# ESP_BASE.net
KiCad netlist of a schematic drawn in Altium Designer
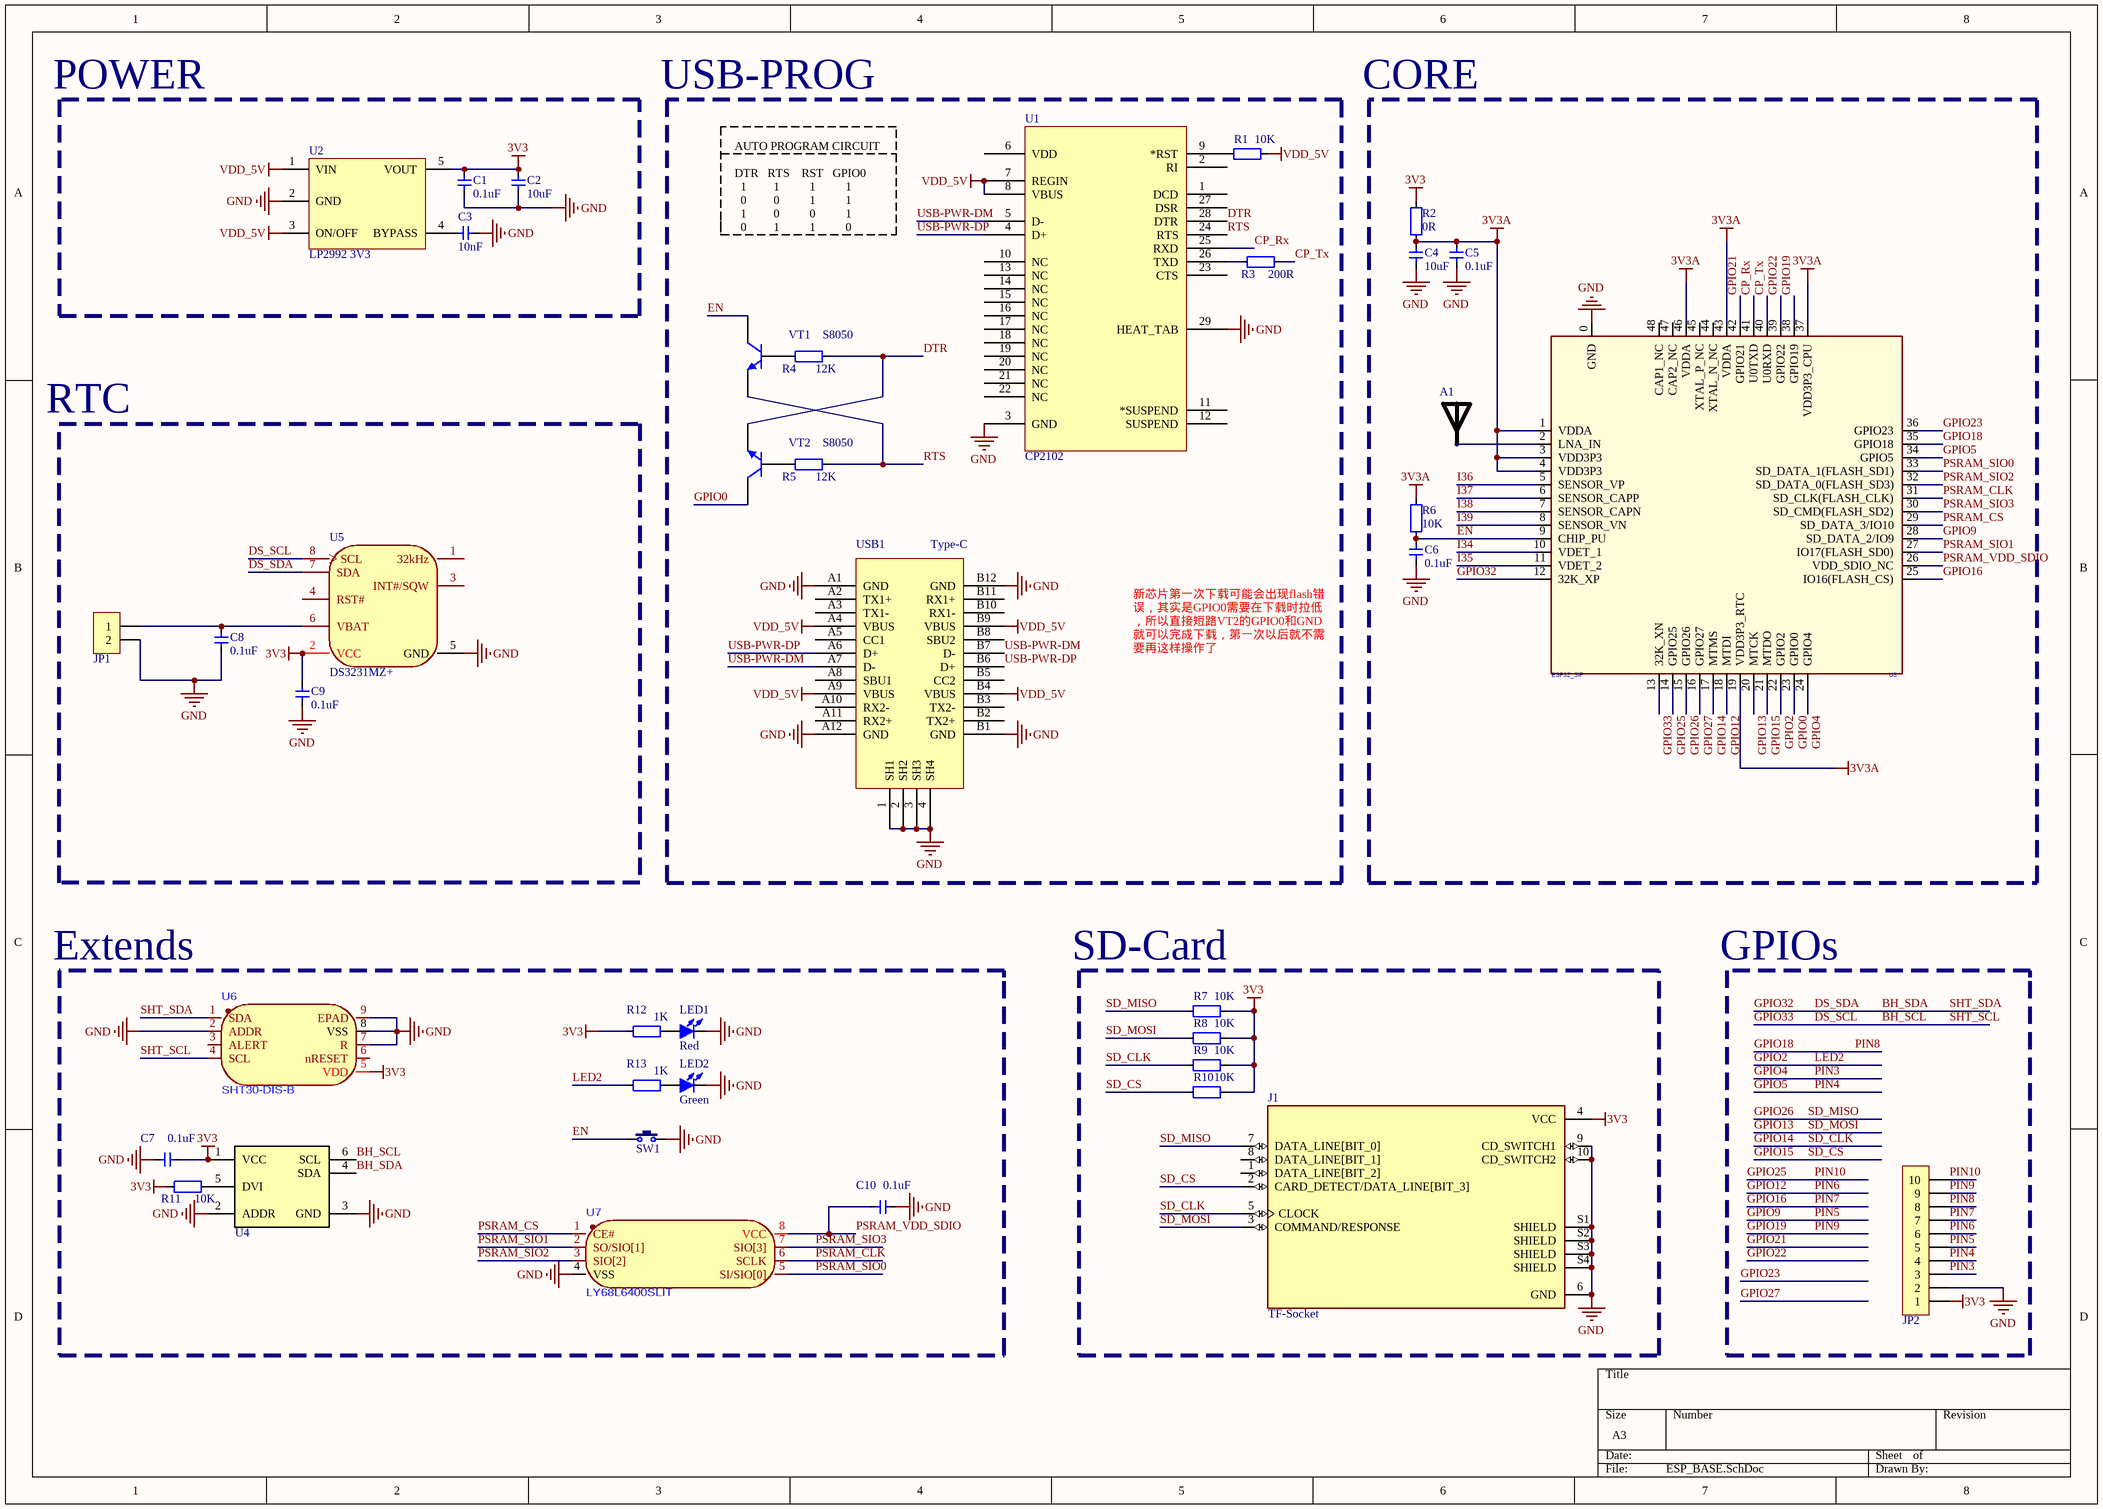
[diagram p0: ESP_BASE.SchDoc]

(export (version "E")
  (design (tool "Eeschema 10.0.6"))
  (components
    (comp (ref "A1")
      (value "RAINSUN")
      (footprint "ANT-Rainsun-AN5120")
      (libsource (lib "MyLib") (part "ANT-Rainsun-AP5120"))
    )
    (comp (ref "C1")
      (value "0.1uF")
      (footprint "CAP_0402")
      (description "Capacitor")
      (libsource (lib "MyLib") (part "电容-0402"))
    )
    (comp (ref "C2")
      (value "10uF")
      (footprint "CAP_0402")
      (description "Capacitor")
      (libsource (lib "MyLib") (part "电容-0402"))
    )
    (comp (ref "C3")
      (value "10nF")
      (footprint "CAP_0402")
      (description "Capacitor")
      (libsource (lib "MyLib") (part "电容-0402"))
    )
    (comp (ref "C4")
      (value "10uF")
      (footprint "CAP_0402")
      (description "Capacitor")
      (libsource (lib "MyLib") (part "电容-0402"))
    )
    (comp (ref "C5")
      (value "0.1uF")
      (footprint "CAP_0402")
      (description "Capacitor")
      (libsource (lib "MyLib") (part "电容-0402"))
    )
    (comp (ref "C6")
      (value "0.1uF")
      (footprint "CAP_0402")
      (description "Capacitor")
      (libsource (lib "MyLib") (part "电容-0402"))
    )
    (comp (ref "C7")
      (value "0.1uF")
      (footprint "CAP_0402")
      (description "Capacitor")
      (libsource (lib "MyLib") (part "电容-0402"))
    )
    (comp (ref "C8")
      (value "0.1uF")
      (footprint "CAP_0402")
      (description "Capacitor")
      (libsource (lib "MyLib") (part "电容-0402"))
    )
    (comp (ref "C9")
      (value "0.1uF")
      (footprint "CAP_0402")
      (description "Capacitor")
      (libsource (lib "MyLib") (part "电容-0402"))
    )
    (comp (ref "C10")
      (value "0.1uF")
      (footprint "CAP_0402")
      (description "Capacitor")
      (libsource (lib "MyLib") (part "电容-0402"))
    )
    (comp (ref "J1")
      (value "TF-Socket")
      (footprint "TF-Card-Amphenol with TF")
      (description "10 _8 + 2_ Position Card Connector Secure Digital - microSDâ„¢ Surface Mount, Right Angle Gold")
      (fields (field (name "MP") "1140084168") (field (name "MF") "Amphenol Commercial Products"))
      (libsource (lib "MyLib") (part "TF-Socket"))
    )
    (comp (ref "JP1")
      (value "MX 1.25-WS-2P")
      (footprint "MX 1.25-WS-2P")
      (description "2P接插件")
      (libsource (lib "MyLib") (part "MX 1.25-WS-2P"))
    )
    (comp (ref "JP2")
      (value "HDR-1X10")
      (footprint "HDR2.54-LI-10P")
      (description "10P接插件")
      (libsource (lib "MyLib") (part "Header 10"))
    )
    (comp (ref "LED1")
      (value "Red")
      (footprint "LED 0603R")
      (description "贴片LED")
      (libsource (lib "MyLib") (part "LED-SMD"))
    )
    (comp (ref "LED2")
      (value "Green")
      (footprint "LED 0603G")
      (description "贴片LED")
      (libsource (lib "MyLib") (part "LED-SMD"))
    )
    (comp (ref "R1")
      (value "10K")
      (footprint "RES_0402")
      (description "Resistor")
      (libsource (lib "MyLib") (part "电阻-0402"))
    )
    (comp (ref "R2")
      (value "0R")
      (footprint "RES_0402")
      (description "Resistor")
      (libsource (lib "") (part "电阻-0402_1"))
    )
    (comp (ref "R3")
      (value "200R")
      (footprint "RES_0402")
      (description "Resistor")
      (libsource (lib "MyLib") (part "电阻-0402"))
    )
    (comp (ref "R4")
      (value "12K")
      (footprint "RES_0402")
      (description "Resistor")
      (libsource (lib "MyLib") (part "电阻-0402"))
    )
    (comp (ref "R5")
      (value "12K")
      (footprint "RES_0402")
      (description "Resistor")
      (libsource (lib "MyLib") (part "电阻-0402"))
    )
    (comp (ref "R6")
      (value "10K")
      (footprint "RES_0402")
      (description "Resistor")
      (libsource (lib "") (part "电阻-0402_1"))
    )
    (comp (ref "R7")
      (value "10K")
      (footprint "RES_0402")
      (description "Resistor")
      (libsource (lib "MyLib") (part "电阻-0402"))
    )
    (comp (ref "R8")
      (value "10K")
      (footprint "RES_0402")
      (description "Resistor")
      (libsource (lib "MyLib") (part "电阻-0402"))
    )
    (comp (ref "R9")
      (value "10K")
      (footprint "RES_0402")
      (description "Resistor")
      (libsource (lib "MyLib") (part "电阻-0402"))
    )
    (comp (ref "R10")
      (value "10K")
      (footprint "RES_0402")
      (description "Resistor")
      (libsource (lib "MyLib") (part "电阻-0402"))
    )
    (comp (ref "R11")
      (value "10K")
      (footprint "RES_0402")
      (description "Resistor")
      (libsource (lib "MyLib") (part "电阻-0402"))
    )
    (comp (ref "R12")
      (value "1K")
      (footprint "RES_0402")
      (description "Resistor")
      (libsource (lib "MyLib") (part "电阻-0402"))
    )
    (comp (ref "R13")
      (value "1K")
      (footprint "RES_0402")
      (description "Resistor")
      (libsource (lib "MyLib") (part "电阻-0402"))
    )
    (comp (ref "SW1")
      (value "3x6x5")
      (footprint "TSW SMD-3*6*2.5")
      (description "3x6轻触开关")
      (libsource (lib "MyLib") (part "TSW 3x6"))
    )
    (comp (ref "U1")
      (value "CP2102")
      (footprint "QFN-28")
      (description "USB转TTL")
      (libsource (lib "MyLib") (part "CP2102"))
    )
    (comp (ref "U2")
      (value "LP2992 3V3")
      (footprint "SOT23-5")
      (description "LDO")
      (libsource (lib "MyLib") (part "LP2992"))
    )
    (comp (ref "U3")
      (value "ESP32_SIP")
      (footprint "QFN-48_7X7")
      (libsource (lib "MyLib") (part "ESP32-PICO"))
    )
    (comp (ref "U4")
      (value "BH1750FVI-TR")
      (footprint "BH1750FVI")
      (libsource (lib "MyLib") (part "BH1750FVI-TR"))
    )
    (comp (ref "U5") (value "DS3231MZ+") (footprint "SO8_L") (libsource (lib "MyLib") (part "DS3231MZ+")))
    (comp (ref "U6")
      (value "SHT30-DIS-B")
      (footprint "DFN-8_L2.5-W2.5-P0.50-BL-EP")
      (libsource (lib "MyLib") (part "SHT30-DIS-B"))
    )
    (comp (ref "U7")
      (value "LY68L6400SLIT")
      (footprint "SOP-8_150MIL")
      (description "PSRAM")
      (libsource (lib "MyLib") (part "LY68L6400SLIT"))
    )
    (comp (ref "USB1")
      (value "Type-C")
      (footprint "Type-C-TOP")
      (libsource (lib "MyLib") (part "USB-Type-C-TOP"))
    )
    (comp (ref "VT1")
      (value "S8050")
      (footprint "SMT_TRIODE_NPN")
      (description "Surface mount NPN transistor, package SOT-23")
      (libsource (lib "MyLib") (part "SMT_TRIODE_NPN"))
    )
    (comp (ref "VT2")
      (value "S8050")
      (footprint "SMT_TRIODE_NPN")
      (description "Surface mount NPN transistor, package SOT-23")
      (libsource (lib "MyLib") (part "SMT_TRIODE_NPN"))
    )
  )
  (nets
    (net (code "1") (name "/BH_SCL") (class "Default")
      (node (ref "U3") (pin "13") (pinfunction "32K_XN_13") (pintype "passive"))
      (node (ref "U4") (pin "6") (pinfunction "SCL_6") (pintype "passive"))
      (node (ref "U5") (pin "8") (pinfunction "SCL_8") (pintype "passive"))
      (node (ref "U6") (pin "4") (pinfunction "SCL_4") (pintype "passive"))
    )
    (net (code "2") (name "/BH_SDA") (class "Default")
      (node (ref "U3") (pin "12") (pinfunction "32K_XP_12") (pintype "passive"))
      (node (ref "U4") (pin "4") (pinfunction "SDA_4") (pintype "passive"))
      (node (ref "U5") (pin "7") (pinfunction "SDA_7") (pintype "passive"))
      (node (ref "U6") (pin "1") (pinfunction "SDA_1") (pintype "passive"))
    )
    (net (code "3") (name "/CP_Rx") (class "Default")
      (node (ref "U1") (pin "25") (pinfunction "RXD_25") (pintype "passive"))
      (node (ref "U3") (pin "41") (pinfunction "U0TXD_41") (pintype "power_in"))
    )
    (net (code "4") (name "/CP_Tx") (class "Default")
      (node (ref "R3") (pin "1") (pinfunction "1_1") (pintype "passive"))
      (node (ref "U3") (pin "40") (pinfunction "U0RXD_40") (pintype "power_in"))
    )
    (net (code "5") (name "/DTR") (class "Default")
      (node (ref "R4") (pin "1") (pinfunction "1_1") (pintype "passive"))
      (node (ref "U1") (pin "28") (pinfunction "DTR_28") (pintype "passive"))
      (node (ref "VT2") (pin "2") (pinfunction "E_2") (pintype "passive"))
    )
    (net (code "6") (name "/EN") (class "Default")
      (node (ref "C6") (pin "1") (pinfunction "1_1") (pintype "passive"))
      (node (ref "R6") (pin "2") (pinfunction "2_2") (pintype "passive"))
      (node (ref "SW1") (pin "1") (pinfunction "1_1") (pintype "passive"))
      (node (ref "U3") (pin "9") (pinfunction "CHIP_PU_9") (pintype "passive"))
      (node (ref "VT1") (pin "3") (pinfunction "C_3") (pintype "passive"))
    )
    (net (code "7") (name "/GPIO0") (class "Default")
      (node (ref "U3") (pin "23") (pinfunction "GPIO0_23") (pintype "passive"))
      (node (ref "VT2") (pin "3") (pinfunction "C_3") (pintype "passive"))
    )
    (net (code "8") (name "/GPIO2") (class "Default")
      (node (ref "R13") (pin "2") (pinfunction "2_2") (pintype "passive"))
      (node (ref "U3") (pin "22") (pinfunction "GPIO2_22") (pintype "passive"))
    )
    (net (code "9") (name "/GPIO4") (class "Default")
      (node (ref "JP2") (pin "3") (pinfunction "3_3") (pintype "passive"))
      (node (ref "U3") (pin "24") (pinfunction "GPIO4_24") (pintype "passive"))
    )
    (net (code "10") (name "/GPIO5") (class "Default")
      (node (ref "JP2") (pin "4") (pinfunction "4_4") (pintype "passive"))
      (node (ref "U3") (pin "34") (pinfunction "GPIO5_34") (pintype "passive"))
    )
    (net (code "11") (name "/GPIO9") (class "Default")
      (node (ref "JP2") (pin "5") (pinfunction "5_5") (pintype "passive"))
      (node (ref "U3") (pin "28") (pinfunction "SD_DATA_2/IO9_28") (pintype "passive"))
    )
    (net (code "12") (name "/GPIO12") (class "Default")
      (node (ref "JP2") (pin "6") (pinfunction "6_6") (pintype "passive"))
      (node (ref "U3") (pin "18") (pinfunction "MTDI_18") (pintype "passive"))
    )
    (net (code "13") (name "/GPIO13") (class "Default")
      (node (ref "J1") (pin "3") (pinfunction "COMMAND/RESPONSE_3") (pintype "bidirectional"))
      (node (ref "R8") (pin "2") (pinfunction "2_2") (pintype "passive"))
      (node (ref "U3") (pin "20") (pinfunction "MTCK_20") (pintype "passive"))
    )
    (net (code "14") (name "/GPIO14") (class "Default")
      (node (ref "J1") (pin "5") (pinfunction "CLOCK_5") (pintype "bidirectional"))
      (node (ref "R9") (pin "2") (pinfunction "2_2") (pintype "passive"))
      (node (ref "U3") (pin "17") (pinfunction "MTMS_17") (pintype "passive"))
    )
    (net (code "15") (name "/GPIO15") (class "Default")
      (node (ref "J1") (pin "2") (pinfunction "CARD_DETECT/DATA_LINE[BIT_3]_2") (pintype "bidirectional"))
      (node (ref "R10") (pin "2") (pinfunction "2_2") (pintype "passive"))
      (node (ref "U3") (pin "21") (pinfunction "MTDO_21") (pintype "passive"))
    )
    (net (code "16") (name "/GPIO16") (class "Default")
      (node (ref "JP2") (pin "7") (pinfunction "7_7") (pintype "passive"))
      (node (ref "U3") (pin "25") (pinfunction "IO16(FLASH_CS)_25") (pintype "passive"))
    )
    (net (code "17") (name "/GPIO18") (class "Default")
      (node (ref "JP2") (pin "8") (pinfunction "8_8") (pintype "passive"))
      (node (ref "U3") (pin "35") (pinfunction "GPIO18_35") (pintype "passive"))
    )
    (net (code "18") (name "/GPIO19") (class "Default")
      (node (ref "JP2") (pin "9") (pinfunction "9_9") (pintype "passive"))
      (node (ref "U3") (pin "38") (pinfunction "GPIO19_38") (pintype "passive"))
    )
    (net (code "19") (name "/GPIO21") (class "Default")
      (node (ref "U3") (pin "42") (pinfunction "GPIO21_42") (pintype "passive"))
    )
    (net (code "20") (name "/GPIO22") (class "Default")
      (node (ref "U3") (pin "39") (pinfunction "GPIO22_39") (pintype "passive"))
    )
    (net (code "21") (name "/GPIO23") (class "Default")
      (node (ref "U3") (pin "36") (pinfunction "GPIO23_36") (pintype "passive"))
    )
    (net (code "22") (name "/GPIO25") (class "Default")
      (node (ref "JP2") (pin "10") (pinfunction "10_10") (pintype "passive"))
      (node (ref "U3") (pin "14") (pinfunction "GPIO25_14") (pintype "passive"))
    )
    (net (code "23") (name "/GPIO26") (class "Default")
      (node (ref "J1") (pin "7") (pinfunction "DATA_LINE[BIT_0]_7") (pintype "bidirectional"))
      (node (ref "R7") (pin "2") (pinfunction "2_2") (pintype "passive"))
      (node (ref "U3") (pin "15") (pinfunction "GPIO26_15") (pintype "passive"))
    )
    (net (code "24") (name "/GPIO27") (class "Default")
      (node (ref "U3") (pin "16") (pinfunction "GPIO27_16") (pintype "passive"))
    )
    (net (code "25") (name "/I34") (class "Default")
      (node (ref "U3") (pin "10") (pinfunction "VDET_1_10") (pintype "passive"))
    )
    (net (code "26") (name "/I35") (class "Default")
      (node (ref "U3") (pin "11") (pinfunction "VDET_2_11") (pintype "passive"))
    )
    (net (code "27") (name "/I36") (class "Default")
      (node (ref "U3") (pin "5") (pinfunction "SENSOR_VP_5") (pintype "passive"))
    )
    (net (code "28") (name "/I37") (class "Default")
      (node (ref "U3") (pin "6") (pinfunction "SENSOR_CAPP_6") (pintype "passive"))
    )
    (net (code "29") (name "/I38") (class "Default")
      (node (ref "U3") (pin "7") (pinfunction "SENSOR_CAPN_7") (pintype "passive"))
    )
    (net (code "30") (name "/I39") (class "Default")
      (node (ref "U3") (pin "8") (pinfunction "SENSOR_VN_8") (pintype "passive"))
    )
    (net (code "31") (name "/PSRAM_CLK") (class "Default")
      (node (ref "U3") (pin "31") (pinfunction "SD_CLK(FLASH_CLK)_31") (pintype "passive"))
      (node (ref "U7") (pin "6") (pinfunction "SCLK_6") (pintype "passive"))
    )
    (net (code "32") (name "/PSRAM_CS") (class "Default")
      (node (ref "U3") (pin "29") (pinfunction "SD_DATA_3/IO10_29") (pintype "passive"))
      (node (ref "U7") (pin "1") (pinfunction "CE#_1") (pintype "passive"))
    )
    (net (code "33") (name "/PSRAM_SIO0") (class "Default")
      (node (ref "U3") (pin "33") (pinfunction "SD_DATA_1(FLASH_SD1)_33") (pintype "passive"))
      (node (ref "U7") (pin "5") (pinfunction "SI/SIO[0]_5") (pintype "passive"))
    )
    (net (code "34") (name "/PSRAM_SIO1") (class "Default")
      (node (ref "U3") (pin "27") (pinfunction "IO17(FLASH_SD0)_27") (pintype "passive"))
      (node (ref "U7") (pin "2") (pinfunction "SO/SIO[1]_2") (pintype "passive"))
    )
    (net (code "35") (name "/PSRAM_SIO2") (class "Default")
      (node (ref "U3") (pin "32") (pinfunction "SD_DATA_0(FLASH_SD3)_32") (pintype "passive"))
      (node (ref "U7") (pin "3") (pinfunction "SIO[2]_3") (pintype "passive"))
    )
    (net (code "36") (name "/PSRAM_SIO3") (class "Default")
      (node (ref "U3") (pin "30") (pinfunction "SD_CMD(FLASH_SD2)_30") (pintype "passive"))
      (node (ref "U7") (pin "7") (pinfunction "SIO[3]_7") (pintype "passive"))
    )
    (net (code "37") (name "/PSRAM_VDD_SDIO") (class "Default")
      (node (ref "C10") (pin "2") (pinfunction "2_2") (pintype "passive"))
      (node (ref "U3") (pin "26") (pinfunction "VDD_SDIO_NC_26") (pintype "passive"))
      (node (ref "U7") (pin "8") (pinfunction "VCC_8") (pintype "passive"))
    )
    (net (code "38") (name "/RTS") (class "Default")
      (node (ref "R5") (pin "1") (pinfunction "1_1") (pintype "passive"))
      (node (ref "U1") (pin "24") (pinfunction "RTS_24") (pintype "passive"))
      (node (ref "VT1") (pin "2") (pinfunction "E_2") (pintype "passive"))
    )
    (net (code "39") (name "/USB-PWR-DM") (class "Default")
      (node (ref "U1") (pin "5") (pinfunction "D-_5") (pintype "passive"))
      (node (ref "USB1") (pin "A7") (pinfunction "D-_A7") (pintype "passive"))
      (node (ref "USB1") (pin "B7") (pinfunction "D-_B7") (pintype "passive"))
    )
    (net (code "40") (name "/USB-PWR-DP") (class "Default")
      (node (ref "U1") (pin "4") (pinfunction "D+_4") (pintype "passive"))
      (node (ref "USB1") (pin "A6") (pinfunction "D+_A6") (pintype "passive"))
      (node (ref "USB1") (pin "B6") (pinfunction "D+_B6") (pintype "passive"))
    )
    (net (code "41") (name "3V3") (class "Default")
      (node (ref "C1") (pin "2") (pinfunction "2_2") (pintype "passive"))
      (node (ref "C2") (pin "2") (pinfunction "2_2") (pintype "passive"))
      (node (ref "C7") (pin "1") (pinfunction "1_1") (pintype "passive"))
      (node (ref "C9") (pin "1") (pinfunction "1_1") (pintype "passive"))
      (node (ref "J1") (pin "4") (pinfunction "VCC_4") (pintype "power_in"))
      (node (ref "JP2") (pin "1") (pinfunction "1_1") (pintype "passive"))
      (node (ref "R10") (pin "1") (pinfunction "1_1") (pintype "passive"))
      (node (ref "R11") (pin "2") (pinfunction "2_2") (pintype "passive"))
      (node (ref "R12") (pin "2") (pinfunction "2_2") (pintype "passive"))
      (node (ref "R2") (pin "1") (pinfunction "1_1") (pintype "passive"))
      (node (ref "R7") (pin "1") (pinfunction "1_1") (pintype "passive"))
      (node (ref "R8") (pin "1") (pinfunction "1_1") (pintype "passive"))
      (node (ref "R9") (pin "1") (pinfunction "1_1") (pintype "passive"))
      (node (ref "U2") (pin "5") (pinfunction "VOUT_5") (pintype "passive"))
      (node (ref "U4") (pin "1") (pinfunction "VCC_1") (pintype "passive"))
      (node (ref "U5") (pin "2") (pinfunction "VCC_2") (pintype "passive"))
      (node (ref "U6") (pin "5") (pinfunction "VDD_5") (pintype "passive"))
    )
    (net (code "42") (name "3V3A") (class "Default")
      (node (ref "C4") (pin "2") (pinfunction "2_2") (pintype "passive"))
      (node (ref "C5") (pin "2") (pinfunction "2_2") (pintype "passive"))
      (node (ref "R2") (pin "2") (pinfunction "2_2") (pintype "passive"))
      (node (ref "R6") (pin "1") (pinfunction "1_1") (pintype "passive"))
      (node (ref "U3") (pin "1") (pinfunction "VDDA_1") (pintype "power_in"))
      (node (ref "U3") (pin "19") (pinfunction "VDD3P3_RTC_19") (pintype "power_in"))
      (node (ref "U3") (pin "3") (pinfunction "VDD3P3_3") (pintype "power_in"))
      (node (ref "U3") (pin "37") (pinfunction "VDD3P3_CPU_37") (pintype "power_in"))
      (node (ref "U3") (pin "4") (pinfunction "VDD3P3_4") (pintype "power_in"))
      (node (ref "U3") (pin "43") (pinfunction "VDDA_43") (pintype "power_in"))
      (node (ref "U3") (pin "46") (pinfunction "VDDA_46") (pintype "power_in"))
    )
    (net (code "43") (name "GND") (class "Default")
      (node (ref "C1") (pin "1") (pinfunction "1_1") (pintype "passive"))
      (node (ref "C10") (pin "1") (pinfunction "1_1") (pintype "passive"))
      (node (ref "C2") (pin "1") (pinfunction "1_1") (pintype "passive"))
      (node (ref "C3") (pin "1") (pinfunction "1_1") (pintype "passive"))
      (node (ref "C4") (pin "1") (pinfunction "1_1") (pintype "passive"))
      (node (ref "C5") (pin "1") (pinfunction "1_1") (pintype "passive"))
      (node (ref "C6") (pin "2") (pinfunction "2_2") (pintype "passive"))
      (node (ref "C7") (pin "2") (pinfunction "2_2") (pintype "passive"))
      (node (ref "C8") (pin "2") (pinfunction "2_2") (pintype "passive"))
      (node (ref "C9") (pin "2") (pinfunction "2_2") (pintype "passive"))
      (node (ref "J1") (pin "10") (pinfunction "CD_SWITCH2_10") (pintype "bidirectional"))
      (node (ref "J1") (pin "6") (pinfunction "GND_6") (pintype "power_in"))
      (node (ref "J1") (pin "9") (pinfunction "CD_SWITCH1_9") (pintype "bidirectional"))
      (node (ref "J1") (pin "S1") (pinfunction "SHIELD_S1") (pintype "passive"))
      (node (ref "J1") (pin "S2") (pinfunction "SHIELD_S2") (pintype "passive"))
      (node (ref "J1") (pin "S3") (pinfunction "SHIELD_S3") (pintype "passive"))
      (node (ref "J1") (pin "S4") (pinfunction "SHIELD_S4") (pintype "passive"))
      (node (ref "JP1") (pin "2") (pinfunction "2_2") (pintype "passive"))
      (node (ref "JP2") (pin "2") (pinfunction "2_2") (pintype "passive"))
      (node (ref "LED1") (pin "2") (pinfunction "K_2") (pintype "passive"))
      (node (ref "LED2") (pin "2") (pinfunction "K_2") (pintype "passive"))
      (node (ref "SW1") (pin "2") (pinfunction "2_2") (pintype "passive"))
      (node (ref "U1") (pin "29") (pinfunction "HEAT_TAB_29") (pintype "passive"))
      (node (ref "U1") (pin "3") (pinfunction "GND_3") (pintype "passive"))
      (node (ref "U2") (pin "2") (pinfunction "GND_2") (pintype "passive"))
      (node (ref "U3") (pin "0") (pinfunction "GND_0") (pintype "power_in"))
      (node (ref "U4") (pin "2") (pinfunction "ADDR_2") (pintype "passive"))
      (node (ref "U4") (pin "3") (pinfunction "GND_3") (pintype "passive"))
      (node (ref "U5") (pin "5") (pinfunction "GND_5") (pintype "passive"))
      (node (ref "U6") (pin "2") (pinfunction "ADDR_2") (pintype "passive"))
      (node (ref "U6") (pin "7") (pinfunction "R_7") (pintype "passive"))
      (node (ref "U6") (pin "8") (pinfunction "VSS_8") (pintype "passive"))
      (node (ref "U6") (pin "9") (pinfunction "EPAD_9") (pintype "passive"))
      (node (ref "U7") (pin "4") (pinfunction "VSS_4") (pintype "passive"))
      (node (ref "USB1") (pin "1") (pinfunction "SH1_1") (pintype "passive"))
      (node (ref "USB1") (pin "2") (pinfunction "SH2_2") (pintype "passive"))
      (node (ref "USB1") (pin "3") (pinfunction "SH3_3") (pintype "passive"))
      (node (ref "USB1") (pin "4") (pinfunction "SH4_4") (pintype "passive"))
      (node (ref "USB1") (pin "A1") (pinfunction "GND_A1") (pintype "passive"))
      (node (ref "USB1") (pin "A12") (pinfunction "GND_A12") (pintype "passive"))
      (node (ref "USB1") (pin "B1") (pinfunction "GND_B1") (pintype "passive"))
      (node (ref "USB1") (pin "B12") (pinfunction "GND_B12") (pintype "passive"))
    )
    (net (code "44") (name "Net-(LED1-A)") (class "Default")
      (node (ref "LED1") (pin "1") (pinfunction "A_1") (pintype "passive"))
      (node (ref "R12") (pin "1") (pinfunction "1_1") (pintype "passive"))
    )
    (net (code "45") (name "Net-(LED2-A)") (class "Default")
      (node (ref "LED2") (pin "1") (pinfunction "A_1") (pintype "passive"))
      (node (ref "R13") (pin "1") (pinfunction "1_1") (pintype "passive"))
    )
    (net (code "46") (name "Net-(U1-*RST)") (class "Default")
      (node (ref "R1") (pin "2") (pinfunction "2_2") (pintype "passive"))
      (node (ref "U1") (pin "9") (pinfunction "*RST_9") (pintype "passive"))
    )
    (net (code "47") (name "Net-(U1-TXD)") (class "Default")
      (node (ref "R3") (pin "2") (pinfunction "2_2") (pintype "passive"))
      (node (ref "U1") (pin "26") (pinfunction "TXD_26") (pintype "passive"))
    )
    (net (code "48") (name "Net-(U2-BYPASS)") (class "Default")
      (node (ref "C3") (pin "2") (pinfunction "2_2") (pintype "passive"))
      (node (ref "U2") (pin "4") (pinfunction "BYPASS_4") (pintype "passive"))
    )
    (net (code "49") (name "Net-(U3-LNA_IN)") (class "Default")
      (node (ref "A1") (pin "1") (pinfunction "1_1") (pintype "passive"))
      (node (ref "U3") (pin "2") (pinfunction "LNA_IN_2") (pintype "passive"))
    )
    (net (code "50") (name "Net-(U4-DVI)") (class "Default")
      (node (ref "R11") (pin "1") (pinfunction "1_1") (pintype "passive"))
      (node (ref "U4") (pin "5") (pinfunction "DVI_5") (pintype "passive"))
    )
    (net (code "51") (name "Net-(U5-VBAT)") (class "Default")
      (node (ref "C8") (pin "1") (pinfunction "1_1") (pintype "passive"))
      (node (ref "JP1") (pin "1") (pinfunction "1_1") (pintype "passive"))
      (node (ref "U5") (pin "6") (pinfunction "VBAT_6") (pintype "passive"))
    )
    (net (code "52") (name "Net-(VT1-B)") (class "Default")
      (node (ref "R4") (pin "2") (pinfunction "2_2") (pintype "passive"))
      (node (ref "VT1") (pin "1") (pinfunction "B_1") (pintype "passive"))
    )
    (net (code "53") (name "Net-(VT2-B)") (class "Default")
      (node (ref "R5") (pin "2") (pinfunction "2_2") (pintype "passive"))
      (node (ref "VT2") (pin "1") (pinfunction "B_1") (pintype "passive"))
    )
    (net (code "54") (name "VDD_5V") (class "Default")
      (node (ref "R1") (pin "1") (pinfunction "1_1") (pintype "passive"))
      (node (ref "U1") (pin "7") (pinfunction "REGIN_7") (pintype "passive"))
      (node (ref "U1") (pin "8") (pinfunction "VBUS_8") (pintype "passive"))
      (node (ref "U2") (pin "1") (pinfunction "VIN_1") (pintype "passive"))
      (node (ref "U2") (pin "3") (pinfunction "ON/OFF_3") (pintype "passive"))
      (node (ref "USB1") (pin "A4") (pinfunction "VBUS_A4") (pintype "passive"))
      (node (ref "USB1") (pin "A9") (pinfunction "VBUS_A9") (pintype "passive"))
      (node (ref "USB1") (pin "B4") (pinfunction "VBUS_B4") (pintype "passive"))
      (node (ref "USB1") (pin "B9") (pinfunction "VBUS_B9") (pintype "passive"))
    )
    (net (code "55") (name "unconnected-(J1-DATA_LINE[BIT_1]-Pad8)") (class "Default")
      (node (ref "J1") (pin "8") (pinfunction "DATA_LINE[BIT_1]_8") (pintype "bidirectional"))
    )
    (net (code "56") (name "unconnected-(J1-DATA_LINE[BIT_2]-Pad1)") (class "Default")
      (node (ref "J1") (pin "1") (pinfunction "DATA_LINE[BIT_2]_1") (pintype "bidirectional"))
    )
    (net (code "57") (name "unconnected-(U1-*SUSPEND-Pad11)") (class "Default")
      (node (ref "U1") (pin "11") (pinfunction "*SUSPEND_11") (pintype "passive"))
    )
    (net (code "58") (name "unconnected-(U1-CTS-Pad23)") (class "Default")
      (node (ref "U1") (pin "23") (pinfunction "CTS_23") (pintype "passive"))
    )
    (net (code "59") (name "unconnected-(U1-DCD-Pad1)") (class "Default")
      (node (ref "U1") (pin "1") (pinfunction "DCD_1") (pintype "passive"))
    )
    (net (code "60") (name "unconnected-(U1-DSR-Pad27)") (class "Default")
      (node (ref "U1") (pin "27") (pinfunction "DSR_27") (pintype "passive"))
    )
    (net (code "61") (name "unconnected-(U1-NC-Pad10)") (class "Default")
      (node (ref "U1") (pin "10") (pinfunction "NC_10") (pintype "passive"))
    )
    (net (code "62") (name "unconnected-(U1-NC-Pad13)") (class "Default")
      (node (ref "U1") (pin "13") (pinfunction "NC_13") (pintype "passive"))
    )
    (net (code "63") (name "unconnected-(U1-NC-Pad14)") (class "Default")
      (node (ref "U1") (pin "14") (pinfunction "NC_14") (pintype "passive"))
    )
    (net (code "64") (name "unconnected-(U1-NC-Pad15)") (class "Default")
      (node (ref "U1") (pin "15") (pinfunction "NC_15") (pintype "passive"))
    )
    (net (code "65") (name "unconnected-(U1-NC-Pad16)") (class "Default")
      (node (ref "U1") (pin "16") (pinfunction "NC_16") (pintype "passive"))
    )
    (net (code "66") (name "unconnected-(U1-NC-Pad17)") (class "Default")
      (node (ref "U1") (pin "17") (pinfunction "NC_17") (pintype "passive"))
    )
    (net (code "67") (name "unconnected-(U1-NC-Pad18)") (class "Default")
      (node (ref "U1") (pin "18") (pinfunction "NC_18") (pintype "passive"))
    )
    (net (code "68") (name "unconnected-(U1-NC-Pad19)") (class "Default")
      (node (ref "U1") (pin "19") (pinfunction "NC_19") (pintype "passive"))
    )
    (net (code "69") (name "unconnected-(U1-NC-Pad20)") (class "Default")
      (node (ref "U1") (pin "20") (pinfunction "NC_20") (pintype "passive"))
    )
    (net (code "70") (name "unconnected-(U1-NC-Pad21)") (class "Default")
      (node (ref "U1") (pin "21") (pinfunction "NC_21") (pintype "passive"))
    )
    (net (code "71") (name "unconnected-(U1-NC-Pad22)") (class "Default")
      (node (ref "U1") (pin "22") (pinfunction "NC_22") (pintype "passive"))
    )
    (net (code "72") (name "unconnected-(U1-RI-Pad2)") (class "Default")
      (node (ref "U1") (pin "2") (pinfunction "RI_2") (pintype "passive"))
    )
    (net (code "73") (name "unconnected-(U1-SUSPEND-Pad12)") (class "Default")
      (node (ref "U1") (pin "12") (pinfunction "SUSPEND_12") (pintype "passive"))
    )
    (net (code "74") (name "unconnected-(U1-VDD-Pad6)") (class "Default")
      (node (ref "U1") (pin "6") (pinfunction "VDD_6") (pintype "passive"))
    )
    (net (code "75") (name "unconnected-(U3-CAP1_NC-Pad48)") (class "Default")
      (node (ref "U3") (pin "48") (pinfunction "CAP1_NC_48") (pintype "passive"))
    )
    (net (code "76") (name "unconnected-(U3-CAP2_NC-Pad47)") (class "Default")
      (node (ref "U3") (pin "47") (pinfunction "CAP2_NC_47") (pintype "passive"))
    )
    (net (code "77") (name "unconnected-(U3-XTAL_N_NC-Pad44)") (class "Default")
      (node (ref "U3") (pin "44") (pinfunction "XTAL_N_NC_44") (pintype "passive"))
    )
    (net (code "78") (name "unconnected-(U3-XTAL_P_NC-Pad45)") (class "Default")
      (node (ref "U3") (pin "45") (pinfunction "XTAL_P_NC_45") (pintype "passive"))
    )
    (net (code "79") (name "unconnected-(U5-32kHz-Pad1)") (class "Default")
      (node (ref "U5") (pin "1") (pinfunction "32kHz_1") (pintype "passive"))
    )
    (net (code "80") (name "unconnected-(U5-INT#{slash}SQW-Pad3)") (class "Default")
      (node (ref "U5") (pin "3") (pinfunction "INT#/SQW_3") (pintype "passive"))
    )
    (net (code "81") (name "unconnected-(U5-RST#-Pad4)") (class "Default")
      (node (ref "U5") (pin "4") (pinfunction "RST#_4") (pintype "passive"))
    )
    (net (code "82") (name "unconnected-(U6-ALERT-Pad3)") (class "Default")
      (node (ref "U6") (pin "3") (pinfunction "ALERT_3") (pintype "passive"))
    )
    (net (code "83") (name "unconnected-(U6-nRESET-Pad6)") (class "Default")
      (node (ref "U6") (pin "6") (pinfunction "nRESET_6") (pintype "passive"))
    )
    (net (code "84") (name "unconnected-(USB1-CC1-PadA5)") (class "Default")
      (node (ref "USB1") (pin "A5") (pinfunction "CC1_A5") (pintype "passive"))
    )
    (net (code "85") (name "unconnected-(USB1-CC2-PadB5)") (class "Default")
      (node (ref "USB1") (pin "B5") (pinfunction "CC2_B5") (pintype "passive"))
    )
    (net (code "86") (name "unconnected-(USB1-RX1+-PadB11)") (class "Default")
      (node (ref "USB1") (pin "B11") (pinfunction "RX1+_B11") (pintype "passive"))
    )
    (net (code "87") (name "unconnected-(USB1-RX1--PadB10)") (class "Default")
      (node (ref "USB1") (pin "B10") (pinfunction "RX1-_B10") (pintype "passive"))
    )
    (net (code "88") (name "unconnected-(USB1-RX2+-PadA11)") (class "Default")
      (node (ref "USB1") (pin "A11") (pinfunction "RX2+_A11") (pintype "passive"))
    )
    (net (code "89") (name "unconnected-(USB1-RX2--PadA10)") (class "Default")
      (node (ref "USB1") (pin "A10") (pinfunction "RX2-_A10") (pintype "passive"))
    )
    (net (code "90") (name "unconnected-(USB1-SBU1-PadA8)") (class "Default")
      (node (ref "USB1") (pin "A8") (pinfunction "SBU1_A8") (pintype "passive"))
    )
    (net (code "91") (name "unconnected-(USB1-SBU2-PadB8)") (class "Default")
      (node (ref "USB1") (pin "B8") (pinfunction "SBU2_B8") (pintype "passive"))
    )
    (net (code "92") (name "unconnected-(USB1-TX1+-PadA2)") (class "Default")
      (node (ref "USB1") (pin "A2") (pinfunction "TX1+_A2") (pintype "passive"))
    )
    (net (code "93") (name "unconnected-(USB1-TX1--PadA3)") (class "Default")
      (node (ref "USB1") (pin "A3") (pinfunction "TX1-_A3") (pintype "passive"))
    )
    (net (code "94") (name "unconnected-(USB1-TX2+-PadB2)") (class "Default")
      (node (ref "USB1") (pin "B2") (pinfunction "TX2+_B2") (pintype "passive"))
    )
    (net (code "95") (name "unconnected-(USB1-TX2--PadB3)") (class "Default")
      (node (ref "USB1") (pin "B3") (pinfunction "TX2-_B3") (pintype "passive"))
    )
  )
)
